# moistureSensor.net
KiCad netlist of a schematic drawn in EAGLE
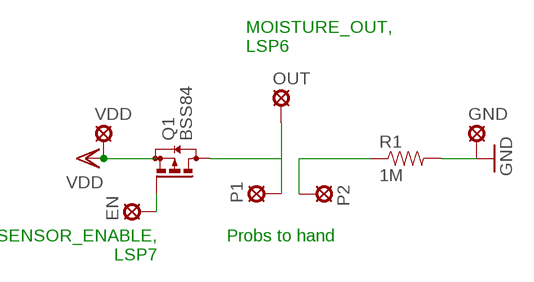
[diagram p0: schematic, sheet 1]

(export (version "E")
  (design (tool "Eeschema 10.0.6"))
  (components
    (comp (ref "EN")
      (value "MCS10B")
      (footprint "eagle-import:MCS10B")
      (libsource (lib "eagle-import") (part "MCS10B"))
    )
    (comp (ref "GND")
      (value "MCS10B")
      (footprint "eagle-import:MCS10B")
      (libsource (lib "eagle-import") (part "MCS10B"))
    )
    (comp (ref "OUT")
      (value "MCS10B")
      (footprint "eagle-import:MCS10B")
      (libsource (lib "eagle-import") (part "MCS10B"))
    )
    (comp (ref "P1")
      (value "MCS10B")
      (footprint "eagle-import:MCS10B")
      (libsource (lib "eagle-import") (part "MCS10B"))
    )
    (comp (ref "P2")
      (value "MCS10B")
      (footprint "eagle-import:MCS10B")
      (libsource (lib "eagle-import") (part "MCS10B"))
    )
    (comp (ref "Q1")
      (value "BSS84")
      (footprint "eagle-import:SOT23")
      (libsource (lib "eagle-import") (part "BSS84"))
    )
    (comp (ref "R1")
      (value "1M")
      (footprint "eagle-import:0603-RES")
      (libsource (lib "eagle-import") (part "1MOHM-1/10W-1%(0603)"))
    )
    (comp (ref "VDD")
      (value "MCS10B")
      (footprint "eagle-import:MCS10B")
      (libsource (lib "eagle-import") (part "MCS10B"))
    )
  )
  (nets
    (net (code "1") (name "GND") (class "Default")
      (node (ref "GND") (pin "MP") (pinfunction "MP_MP") (pintype "passive"))
      (node (ref "R1") (pin "2") (pinfunction "2_2") (pintype "passive"))
    )
    (net (code "2") (name "Net-(P2-PadMP)") (class "Default")
      (node (ref "P2") (pin "MP") (pinfunction "MP_MP") (pintype "passive"))
      (node (ref "R1") (pin "1") (pinfunction "1_1") (pintype "passive"))
    )
    (net (code "3") (name "Net-(Q1-D)") (class "Default")
      (node (ref "OUT") (pin "MP") (pinfunction "MP_MP") (pintype "passive"))
      (node (ref "P1") (pin "MP") (pinfunction "MP_MP") (pintype "passive"))
      (node (ref "Q1") (pin "3") (pinfunction "D_3") (pintype "passive"))
    )
    (net (code "4") (name "Net-(Q1-G)") (class "Default")
      (node (ref "EN") (pin "MP") (pinfunction "MP_MP") (pintype "passive"))
      (node (ref "Q1") (pin "1") (pinfunction "G_1") (pintype "passive"))
    )
    (net (code "5") (name "VDD") (class "Default")
      (node (ref "Q1") (pin "2") (pinfunction "S_2") (pintype "passive"))
      (node (ref "VDD") (pin "MP") (pinfunction "MP_MP") (pintype "passive"))
    )
  )
)
